# STM32F446_front_pane_-_northwest_-_v3.net
KiCad netlist of a schematic drawn in EAGLE
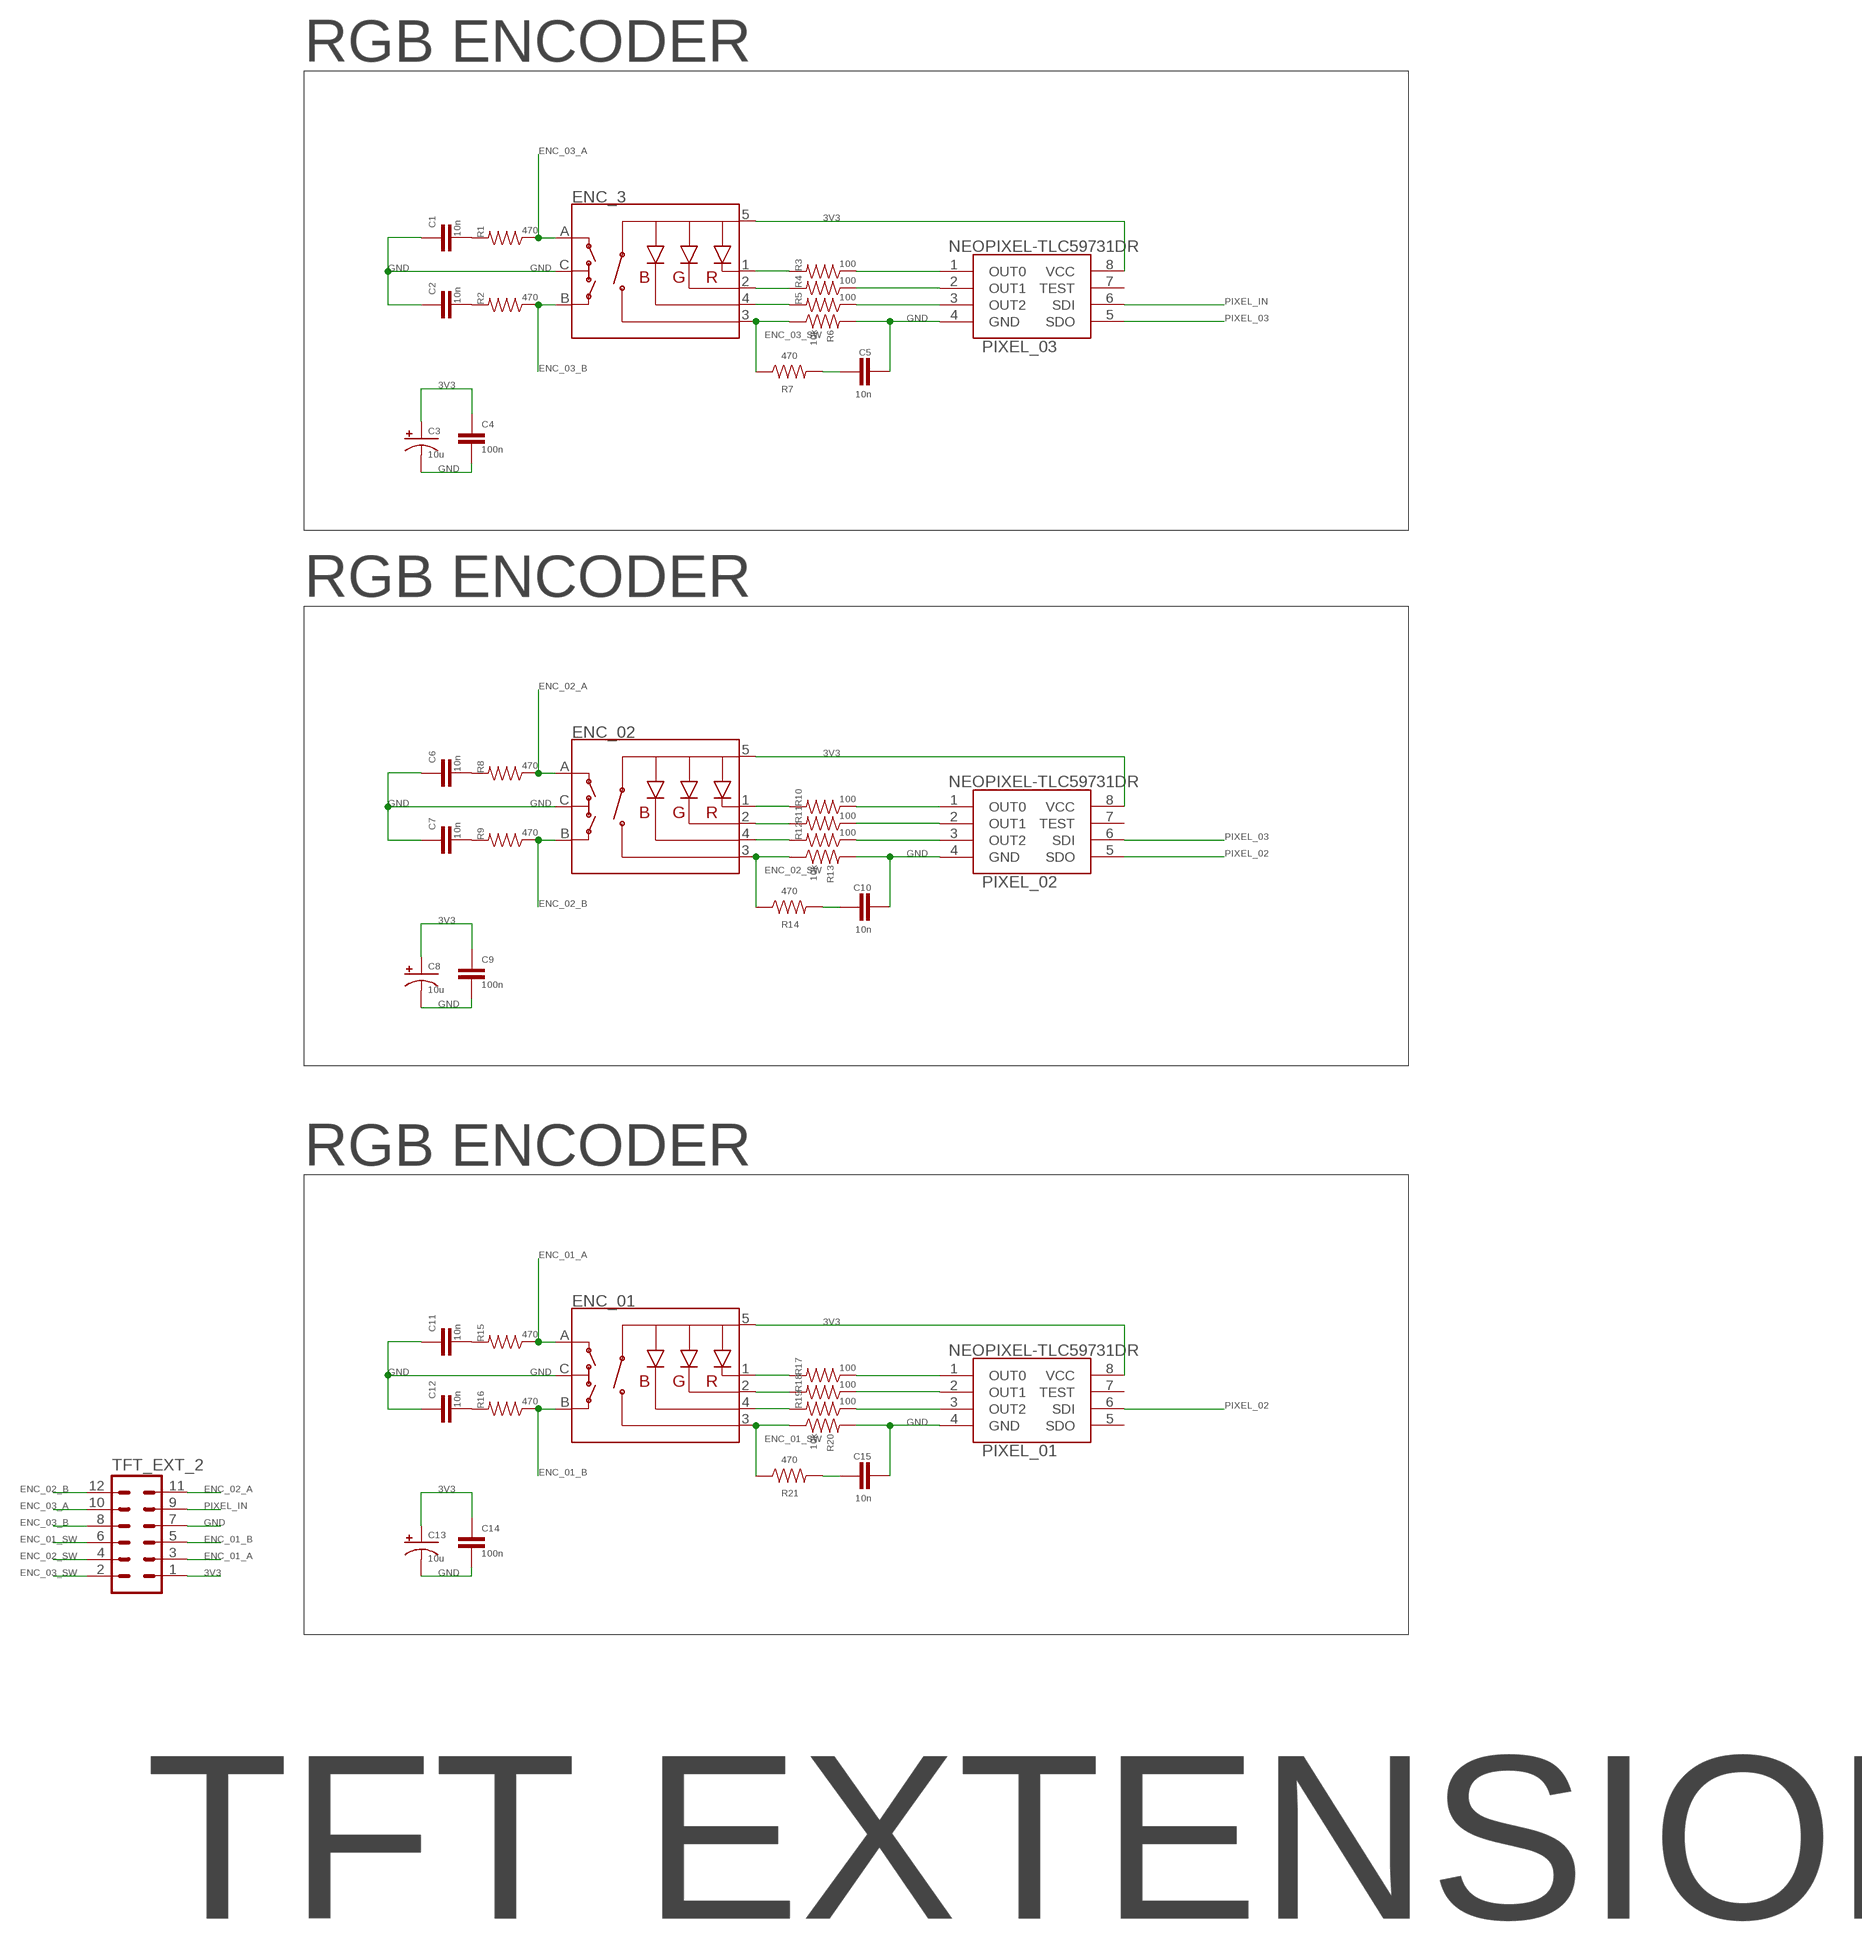
[diagram p0: schematic, sheet 1]

(export (version "E")
  (design (tool "Eeschema 10.0.6"))
  (components
    (comp (ref "C1")
      (value "10n")
      (footprint "eagle-import:0805-CAP")
      (libsource (lib "eagle-import") (part "PASSIF-CAP-0805"))
    )
    (comp (ref "C2")
      (value "10n")
      (footprint "eagle-import:0805-CAP")
      (libsource (lib "eagle-import") (part "PASSIF-CAP-0805"))
    )
    (comp (ref "C3")
      (value "10u")
      (footprint "eagle-import:CPOL2917")
      (libsource (lib "eagle-import") (part "PASSIF-CPOL-US2917"))
    )
    (comp (ref "C4")
      (value "100n")
      (footprint "eagle-import:0805-CAP")
      (libsource (lib "eagle-import") (part "PASSIF-CAP-0805"))
    )
    (comp (ref "C5")
      (value "10n")
      (footprint "eagle-import:0805-CAP")
      (libsource (lib "eagle-import") (part "PASSIF-CAP-0805"))
    )
    (comp (ref "C6")
      (value "10n")
      (footprint "eagle-import:0805-CAP")
      (libsource (lib "eagle-import") (part "PASSIF-CAP-0805"))
    )
    (comp (ref "C7")
      (value "10n")
      (footprint "eagle-import:0805-CAP")
      (libsource (lib "eagle-import") (part "PASSIF-CAP-0805"))
    )
    (comp (ref "C8")
      (value "10u")
      (footprint "eagle-import:CPOL2917")
      (libsource (lib "eagle-import") (part "PASSIF-CPOL-US2917"))
    )
    (comp (ref "C9")
      (value "100n")
      (footprint "eagle-import:0805-CAP")
      (libsource (lib "eagle-import") (part "PASSIF-CAP-0805"))
    )
    (comp (ref "C10")
      (value "10n")
      (footprint "eagle-import:0805-CAP")
      (libsource (lib "eagle-import") (part "PASSIF-CAP-0805"))
    )
    (comp (ref "C11")
      (value "10n")
      (footprint "eagle-import:0805-CAP")
      (libsource (lib "eagle-import") (part "PASSIF-CAP-0805"))
    )
    (comp (ref "C12")
      (value "10n")
      (footprint "eagle-import:0805-CAP")
      (libsource (lib "eagle-import") (part "PASSIF-CAP-0805"))
    )
    (comp (ref "C13")
      (value "10u")
      (footprint "eagle-import:CPOL2917")
      (libsource (lib "eagle-import") (part "PASSIF-CPOL-US2917"))
    )
    (comp (ref "C14")
      (value "100n")
      (footprint "eagle-import:0805-CAP")
      (libsource (lib "eagle-import") (part "PASSIF-CAP-0805"))
    )
    (comp (ref "C15")
      (value "10n")
      (footprint "eagle-import:0805-CAP")
      (libsource (lib "eagle-import") (part "PASSIF-CAP-0805"))
    )
    (comp (ref "ENC_01")
      (value "ENCODER-RGB-SWITCH-NO_NUT")
      (footprint "eagle-import:ENCODER_LED_3")
      (libsource (lib "eagle-import") (part "ENCODER-RGB-SWITCH-NO_NUT"))
    )
    (comp (ref "ENC_02")
      (value "ENCODER-RGB-SWITCH-NO_NUT")
      (footprint "eagle-import:ENCODER_LED_3")
      (libsource (lib "eagle-import") (part "ENCODER-RGB-SWITCH-NO_NUT"))
    )
    (comp (ref "ENC_3")
      (value "ENCODER-RGB-SWITCH-NO_NUT")
      (footprint "eagle-import:ENCODER_LED_3")
      (libsource (lib "eagle-import") (part "ENCODER-RGB-SWITCH-NO_NUT"))
    )
    (comp (ref "PIXEL_01")
      (value "NEOPIXEL-TLC59731DR")
      (footprint "eagle-import:SOIC127P600X175-8N")
      (fields
        (field (name "ARROW_PART_NUMBER") "TLC59731DR")
        (field (name "MOUSER_PART_NUMBER") "595-TLC59731DR")
      )
      (libsource (lib "eagle-import") (part "NEOPIXEL-TLC59731DR"))
    )
    (comp (ref "PIXEL_02")
      (value "NEOPIXEL-TLC59731DR")
      (footprint "eagle-import:SOIC127P600X175-8N")
      (fields
        (field (name "ARROW_PART_NUMBER") "TLC59731DR")
        (field (name "MOUSER_PART_NUMBER") "595-TLC59731DR")
      )
      (libsource (lib "eagle-import") (part "NEOPIXEL-TLC59731DR"))
    )
    (comp (ref "PIXEL_03")
      (value "NEOPIXEL-TLC59731DR")
      (footprint "eagle-import:SOIC127P600X175-8N")
      (fields
        (field (name "ARROW_PART_NUMBER") "TLC59731DR")
        (field (name "MOUSER_PART_NUMBER") "595-TLC59731DR")
      )
      (libsource (lib "eagle-import") (part "NEOPIXEL-TLC59731DR"))
    )
    (comp (ref "R1")
      (value "470")
      (footprint "eagle-import:1206")
      (libsource (lib "eagle-import") (part "PASSIF-RESISTOR-1206"))
    )
    (comp (ref "R2")
      (value "470")
      (footprint "eagle-import:1206")
      (libsource (lib "eagle-import") (part "PASSIF-RESISTOR-1206"))
    )
    (comp (ref "R3")
      (value "100")
      (footprint "eagle-import:1206")
      (libsource (lib "eagle-import") (part "PASSIF-RESISTOR-1206"))
    )
    (comp (ref "R4")
      (value "100")
      (footprint "eagle-import:1206")
      (libsource (lib "eagle-import") (part "PASSIF-RESISTOR-1206"))
    )
    (comp (ref "R5")
      (value "100")
      (footprint "eagle-import:1206")
      (libsource (lib "eagle-import") (part "PASSIF-RESISTOR-1206"))
    )
    (comp (ref "R6")
      (value "10k")
      (footprint "eagle-import:1206")
      (libsource (lib "eagle-import") (part "PASSIF-RESISTOR-1206"))
    )
    (comp (ref "R7")
      (value "470")
      (footprint "eagle-import:1206")
      (libsource (lib "eagle-import") (part "PASSIF-RESISTOR-1206"))
    )
    (comp (ref "R8")
      (value "470")
      (footprint "eagle-import:1206")
      (libsource (lib "eagle-import") (part "PASSIF-RESISTOR-1206"))
    )
    (comp (ref "R9")
      (value "470")
      (footprint "eagle-import:1206")
      (libsource (lib "eagle-import") (part "PASSIF-RESISTOR-1206"))
    )
    (comp (ref "R10")
      (value "100")
      (footprint "eagle-import:1206")
      (libsource (lib "eagle-import") (part "PASSIF-RESISTOR-1206"))
    )
    (comp (ref "R11")
      (value "100")
      (footprint "eagle-import:1206")
      (libsource (lib "eagle-import") (part "PASSIF-RESISTOR-1206"))
    )
    (comp (ref "R12")
      (value "100")
      (footprint "eagle-import:1206")
      (libsource (lib "eagle-import") (part "PASSIF-RESISTOR-1206"))
    )
    (comp (ref "R13")
      (value "10k")
      (footprint "eagle-import:1206")
      (libsource (lib "eagle-import") (part "PASSIF-RESISTOR-1206"))
    )
    (comp (ref "R14")
      (value "470")
      (footprint "eagle-import:1206")
      (libsource (lib "eagle-import") (part "PASSIF-RESISTOR-1206"))
    )
    (comp (ref "R15")
      (value "470")
      (footprint "eagle-import:1206")
      (libsource (lib "eagle-import") (part "PASSIF-RESISTOR-1206"))
    )
    (comp (ref "R16")
      (value "470")
      (footprint "eagle-import:1206")
      (libsource (lib "eagle-import") (part "PASSIF-RESISTOR-1206"))
    )
    (comp (ref "R17")
      (value "100")
      (footprint "eagle-import:1206")
      (libsource (lib "eagle-import") (part "PASSIF-RESISTOR-1206"))
    )
    (comp (ref "R18")
      (value "100")
      (footprint "eagle-import:1206")
      (libsource (lib "eagle-import") (part "PASSIF-RESISTOR-1206"))
    )
    (comp (ref "R19")
      (value "100")
      (footprint "eagle-import:1206")
      (libsource (lib "eagle-import") (part "PASSIF-RESISTOR-1206"))
    )
    (comp (ref "R20")
      (value "10k")
      (footprint "eagle-import:1206")
      (libsource (lib "eagle-import") (part "PASSIF-RESISTOR-1206"))
    )
    (comp (ref "R21")
      (value "470")
      (footprint "eagle-import:1206")
      (libsource (lib "eagle-import") (part "PASSIF-RESISTOR-1206"))
    )
    (comp (ref "TFT_EXT_2")
      (value "MA06-2")
      (footprint "eagle-import:MA06-2")
      (libsource (lib "eagle-import") (part "MA06-2"))
    )
  )
  (nets
    (net (code "1") (name "/3V3") (class "Default")
      (node (ref "C13") (pin "+") (pinfunction "+_+") (pintype "passive"))
      (node (ref "C14") (pin "1") (pinfunction "1_1") (pintype "passive"))
      (node (ref "C3") (pin "+") (pinfunction "+_+") (pintype "passive"))
      (node (ref "C4") (pin "1") (pinfunction "1_1") (pintype "passive"))
      (node (ref "C8") (pin "+") (pinfunction "+_+") (pintype "passive"))
      (node (ref "C9") (pin "1") (pinfunction "1_1") (pintype "passive"))
      (node (ref "ENC_01") (pin "5") (pinfunction "+_5") (pintype "passive"))
      (node (ref "ENC_02") (pin "5") (pinfunction "+_5") (pintype "passive"))
      (node (ref "ENC_3") (pin "5") (pinfunction "+_5") (pintype "passive"))
      (node (ref "PIXEL_01") (pin "8") (pinfunction "VCC_8") (pintype "bidirectional"))
      (node (ref "PIXEL_02") (pin "8") (pinfunction "VCC_8") (pintype "bidirectional"))
      (node (ref "PIXEL_03") (pin "8") (pinfunction "VCC_8") (pintype "bidirectional"))
      (node (ref "TFT_EXT_2") (pin "1") (pinfunction "1_1") (pintype "passive"))
    )
    (net (code "2") (name "/ENC_01_A") (class "Default")
      (node (ref "ENC_01") (pin "A") (pinfunction "A_A") (pintype "bidirectional"))
      (node (ref "R15") (pin "1") (pinfunction "1_1") (pintype "passive"))
      (node (ref "TFT_EXT_2") (pin "3") (pinfunction "3_3") (pintype "passive"))
    )
    (net (code "3") (name "/ENC_01_B") (class "Default")
      (node (ref "ENC_01") (pin "B") (pinfunction "B_B") (pintype "bidirectional"))
      (node (ref "R16") (pin "1") (pinfunction "1_1") (pintype "passive"))
      (node (ref "TFT_EXT_2") (pin "5") (pinfunction "5_5") (pintype "passive"))
    )
    (net (code "4") (name "/ENC_01_SW") (class "Default")
      (node (ref "ENC_01") (pin "3") (pinfunction "SW_3") (pintype "passive"))
      (node (ref "R20") (pin "1") (pinfunction "1_1") (pintype "passive"))
      (node (ref "R21") (pin "1") (pinfunction "1_1") (pintype "passive"))
      (node (ref "TFT_EXT_2") (pin "6") (pinfunction "6_6") (pintype "passive"))
    )
    (net (code "5") (name "/ENC_02_A") (class "Default")
      (node (ref "ENC_02") (pin "A") (pinfunction "A_A") (pintype "bidirectional"))
      (node (ref "R8") (pin "1") (pinfunction "1_1") (pintype "passive"))
      (node (ref "TFT_EXT_2") (pin "11") (pinfunction "11_11") (pintype "passive"))
    )
    (net (code "6") (name "/ENC_02_B") (class "Default")
      (node (ref "ENC_02") (pin "B") (pinfunction "B_B") (pintype "bidirectional"))
      (node (ref "R9") (pin "1") (pinfunction "1_1") (pintype "passive"))
      (node (ref "TFT_EXT_2") (pin "12") (pinfunction "12_12") (pintype "passive"))
    )
    (net (code "7") (name "/ENC_02_SW") (class "Default")
      (node (ref "ENC_02") (pin "3") (pinfunction "SW_3") (pintype "passive"))
      (node (ref "R13") (pin "1") (pinfunction "1_1") (pintype "passive"))
      (node (ref "R14") (pin "1") (pinfunction "1_1") (pintype "passive"))
      (node (ref "TFT_EXT_2") (pin "4") (pinfunction "4_4") (pintype "passive"))
    )
    (net (code "8") (name "/ENC_03_A") (class "Default")
      (node (ref "ENC_3") (pin "A") (pinfunction "A_A") (pintype "bidirectional"))
      (node (ref "R1") (pin "1") (pinfunction "1_1") (pintype "passive"))
      (node (ref "TFT_EXT_2") (pin "10") (pinfunction "10_10") (pintype "passive"))
    )
    (net (code "9") (name "/ENC_03_B") (class "Default")
      (node (ref "ENC_3") (pin "B") (pinfunction "B_B") (pintype "bidirectional"))
      (node (ref "R2") (pin "1") (pinfunction "1_1") (pintype "passive"))
      (node (ref "TFT_EXT_2") (pin "8") (pinfunction "8_8") (pintype "passive"))
    )
    (net (code "10") (name "/ENC_03_SW") (class "Default")
      (node (ref "ENC_3") (pin "3") (pinfunction "SW_3") (pintype "passive"))
      (node (ref "R6") (pin "1") (pinfunction "1_1") (pintype "passive"))
      (node (ref "R7") (pin "1") (pinfunction "1_1") (pintype "passive"))
      (node (ref "TFT_EXT_2") (pin "2") (pinfunction "2_2") (pintype "passive"))
    )
    (net (code "11") (name "/GND") (class "Default")
      (node (ref "C1") (pin "1") (pinfunction "1_1") (pintype "passive"))
      (node (ref "C10") (pin "2") (pinfunction "2_2") (pintype "passive"))
      (node (ref "C11") (pin "1") (pinfunction "1_1") (pintype "passive"))
      (node (ref "C12") (pin "1") (pinfunction "1_1") (pintype "passive"))
      (node (ref "C13") (pin "-") (pinfunction "-_-") (pintype "passive"))
      (node (ref "C14") (pin "2") (pinfunction "2_2") (pintype "passive"))
      (node (ref "C15") (pin "2") (pinfunction "2_2") (pintype "passive"))
      (node (ref "C2") (pin "1") (pinfunction "1_1") (pintype "passive"))
      (node (ref "C3") (pin "-") (pinfunction "-_-") (pintype "passive"))
      (node (ref "C4") (pin "2") (pinfunction "2_2") (pintype "passive"))
      (node (ref "C5") (pin "2") (pinfunction "2_2") (pintype "passive"))
      (node (ref "C6") (pin "1") (pinfunction "1_1") (pintype "passive"))
      (node (ref "C7") (pin "1") (pinfunction "1_1") (pintype "passive"))
      (node (ref "C8") (pin "-") (pinfunction "-_-") (pintype "passive"))
      (node (ref "C9") (pin "2") (pinfunction "2_2") (pintype "passive"))
      (node (ref "ENC_01") (pin "C") (pinfunction "C_C") (pintype "bidirectional"))
      (node (ref "ENC_02") (pin "C") (pinfunction "C_C") (pintype "bidirectional"))
      (node (ref "ENC_3") (pin "C") (pinfunction "C_C") (pintype "bidirectional"))
      (node (ref "PIXEL_01") (pin "4") (pinfunction "GND_4") (pintype "bidirectional"))
      (node (ref "PIXEL_02") (pin "4") (pinfunction "GND_4") (pintype "bidirectional"))
      (node (ref "PIXEL_03") (pin "4") (pinfunction "GND_4") (pintype "bidirectional"))
      (node (ref "R13") (pin "2") (pinfunction "2_2") (pintype "passive"))
      (node (ref "R20") (pin "2") (pinfunction "2_2") (pintype "passive"))
      (node (ref "R6") (pin "2") (pinfunction "2_2") (pintype "passive"))
      (node (ref "TFT_EXT_2") (pin "7") (pinfunction "7_7") (pintype "passive"))
    )
    (net (code "12") (name "/PIXEL_02") (class "Default")
      (node (ref "PIXEL_01") (pin "6") (pinfunction "SDI_6") (pintype "bidirectional"))
      (node (ref "PIXEL_02") (pin "5") (pinfunction "SDO_5") (pintype "bidirectional"))
    )
    (net (code "13") (name "/PIXEL_03") (class "Default")
      (node (ref "PIXEL_02") (pin "6") (pinfunction "SDI_6") (pintype "bidirectional"))
      (node (ref "PIXEL_03") (pin "5") (pinfunction "SDO_5") (pintype "bidirectional"))
    )
    (net (code "14") (name "/PIXEL_IN") (class "Default")
      (node (ref "PIXEL_03") (pin "6") (pinfunction "SDI_6") (pintype "bidirectional"))
      (node (ref "TFT_EXT_2") (pin "9") (pinfunction "9_9") (pintype "passive"))
    )
    (net (code "15") (name "Net-(C1-Pad2)") (class "Default")
      (node (ref "C1") (pin "2") (pinfunction "2_2") (pintype "passive"))
      (node (ref "R1") (pin "2") (pinfunction "2_2") (pintype "passive"))
    )
    (net (code "16") (name "Net-(C2-Pad2)") (class "Default")
      (node (ref "C2") (pin "2") (pinfunction "2_2") (pintype "passive"))
      (node (ref "R2") (pin "2") (pinfunction "2_2") (pintype "passive"))
    )
    (net (code "17") (name "Net-(C5-Pad1)") (class "Default")
      (node (ref "C5") (pin "1") (pinfunction "1_1") (pintype "passive"))
      (node (ref "R7") (pin "2") (pinfunction "2_2") (pintype "passive"))
    )
    (net (code "18") (name "Net-(C6-Pad2)") (class "Default")
      (node (ref "C6") (pin "2") (pinfunction "2_2") (pintype "passive"))
      (node (ref "R8") (pin "2") (pinfunction "2_2") (pintype "passive"))
    )
    (net (code "19") (name "Net-(C7-Pad2)") (class "Default")
      (node (ref "C7") (pin "2") (pinfunction "2_2") (pintype "passive"))
      (node (ref "R9") (pin "2") (pinfunction "2_2") (pintype "passive"))
    )
    (net (code "20") (name "Net-(C10-Pad1)") (class "Default")
      (node (ref "C10") (pin "1") (pinfunction "1_1") (pintype "passive"))
      (node (ref "R14") (pin "2") (pinfunction "2_2") (pintype "passive"))
    )
    (net (code "21") (name "Net-(C11-Pad2)") (class "Default")
      (node (ref "C11") (pin "2") (pinfunction "2_2") (pintype "passive"))
      (node (ref "R15") (pin "2") (pinfunction "2_2") (pintype "passive"))
    )
    (net (code "22") (name "Net-(C12-Pad2)") (class "Default")
      (node (ref "C12") (pin "2") (pinfunction "2_2") (pintype "passive"))
      (node (ref "R16") (pin "2") (pinfunction "2_2") (pintype "passive"))
    )
    (net (code "23") (name "Net-(C15-Pad1)") (class "Default")
      (node (ref "C15") (pin "1") (pinfunction "1_1") (pintype "passive"))
      (node (ref "R21") (pin "2") (pinfunction "2_2") (pintype "passive"))
    )
    (net (code "24") (name "Net-(ENC_01--B)") (class "Default")
      (node (ref "ENC_01") (pin "4") (pinfunction "-B_4") (pintype "passive"))
      (node (ref "R19") (pin "2") (pinfunction "2_2") (pintype "passive"))
    )
    (net (code "25") (name "Net-(ENC_01--G)") (class "Default")
      (node (ref "ENC_01") (pin "2") (pinfunction "-G_2") (pintype "passive"))
      (node (ref "R18") (pin "2") (pinfunction "2_2") (pintype "passive"))
    )
    (net (code "26") (name "Net-(ENC_01--R)") (class "Default")
      (node (ref "ENC_01") (pin "1") (pinfunction "-R_1") (pintype "passive"))
      (node (ref "R17") (pin "2") (pinfunction "2_2") (pintype "passive"))
    )
    (net (code "27") (name "Net-(ENC_02--B)") (class "Default")
      (node (ref "ENC_02") (pin "4") (pinfunction "-B_4") (pintype "passive"))
      (node (ref "R12") (pin "2") (pinfunction "2_2") (pintype "passive"))
    )
    (net (code "28") (name "Net-(ENC_02--G)") (class "Default")
      (node (ref "ENC_02") (pin "2") (pinfunction "-G_2") (pintype "passive"))
      (node (ref "R11") (pin "2") (pinfunction "2_2") (pintype "passive"))
    )
    (net (code "29") (name "Net-(ENC_02--R)") (class "Default")
      (node (ref "ENC_02") (pin "1") (pinfunction "-R_1") (pintype "passive"))
      (node (ref "R10") (pin "2") (pinfunction "2_2") (pintype "passive"))
    )
    (net (code "30") (name "Net-(ENC_3--B)") (class "Default")
      (node (ref "ENC_3") (pin "4") (pinfunction "-B_4") (pintype "passive"))
      (node (ref "R5") (pin "2") (pinfunction "2_2") (pintype "passive"))
    )
    (net (code "31") (name "Net-(ENC_3--G)") (class "Default")
      (node (ref "ENC_3") (pin "2") (pinfunction "-G_2") (pintype "passive"))
      (node (ref "R4") (pin "2") (pinfunction "2_2") (pintype "passive"))
    )
    (net (code "32") (name "Net-(ENC_3--R)") (class "Default")
      (node (ref "ENC_3") (pin "1") (pinfunction "-R_1") (pintype "passive"))
      (node (ref "R3") (pin "2") (pinfunction "2_2") (pintype "passive"))
    )
    (net (code "33") (name "Net-(PIXEL_01-OUT0)") (class "Default")
      (node (ref "PIXEL_01") (pin "1") (pinfunction "OUT0_1") (pintype "bidirectional"))
      (node (ref "R17") (pin "1") (pinfunction "1_1") (pintype "passive"))
    )
    (net (code "34") (name "Net-(PIXEL_01-OUT1)") (class "Default")
      (node (ref "PIXEL_01") (pin "2") (pinfunction "OUT1_2") (pintype "bidirectional"))
      (node (ref "R18") (pin "1") (pinfunction "1_1") (pintype "passive"))
    )
    (net (code "35") (name "Net-(PIXEL_01-OUT2)") (class "Default")
      (node (ref "PIXEL_01") (pin "3") (pinfunction "OUT2_3") (pintype "bidirectional"))
      (node (ref "R19") (pin "1") (pinfunction "1_1") (pintype "passive"))
    )
    (net (code "36") (name "Net-(PIXEL_02-OUT0)") (class "Default")
      (node (ref "PIXEL_02") (pin "1") (pinfunction "OUT0_1") (pintype "bidirectional"))
      (node (ref "R10") (pin "1") (pinfunction "1_1") (pintype "passive"))
    )
    (net (code "37") (name "Net-(PIXEL_02-OUT1)") (class "Default")
      (node (ref "PIXEL_02") (pin "2") (pinfunction "OUT1_2") (pintype "bidirectional"))
      (node (ref "R11") (pin "1") (pinfunction "1_1") (pintype "passive"))
    )
    (net (code "38") (name "Net-(PIXEL_02-OUT2)") (class "Default")
      (node (ref "PIXEL_02") (pin "3") (pinfunction "OUT2_3") (pintype "bidirectional"))
      (node (ref "R12") (pin "1") (pinfunction "1_1") (pintype "passive"))
    )
    (net (code "39") (name "Net-(PIXEL_03-OUT0)") (class "Default")
      (node (ref "PIXEL_03") (pin "1") (pinfunction "OUT0_1") (pintype "bidirectional"))
      (node (ref "R3") (pin "1") (pinfunction "1_1") (pintype "passive"))
    )
    (net (code "40") (name "Net-(PIXEL_03-OUT1)") (class "Default")
      (node (ref "PIXEL_03") (pin "2") (pinfunction "OUT1_2") (pintype "bidirectional"))
      (node (ref "R4") (pin "1") (pinfunction "1_1") (pintype "passive"))
    )
    (net (code "41") (name "Net-(PIXEL_03-OUT2)") (class "Default")
      (node (ref "PIXEL_03") (pin "3") (pinfunction "OUT2_3") (pintype "bidirectional"))
      (node (ref "R5") (pin "1") (pinfunction "1_1") (pintype "passive"))
    )
    (net (code "42") (name "unconnected-(PIXEL_01-SDO-Pad5)") (class "Default")
      (node (ref "PIXEL_01") (pin "5") (pinfunction "SDO_5") (pintype "bidirectional"))
    )
    (net (code "43") (name "unconnected-(PIXEL_01-TEST-Pad7)") (class "Default")
      (node (ref "PIXEL_01") (pin "7") (pinfunction "TEST_7") (pintype "bidirectional"))
    )
    (net (code "44") (name "unconnected-(PIXEL_02-TEST-Pad7)") (class "Default")
      (node (ref "PIXEL_02") (pin "7") (pinfunction "TEST_7") (pintype "bidirectional"))
    )
    (net (code "45") (name "unconnected-(PIXEL_03-TEST-Pad7)") (class "Default")
      (node (ref "PIXEL_03") (pin "7") (pinfunction "TEST_7") (pintype "bidirectional"))
    )
  )
)
